# NinjaPool-171016.net
KiCad netlist of a schematic drawn in EAGLE
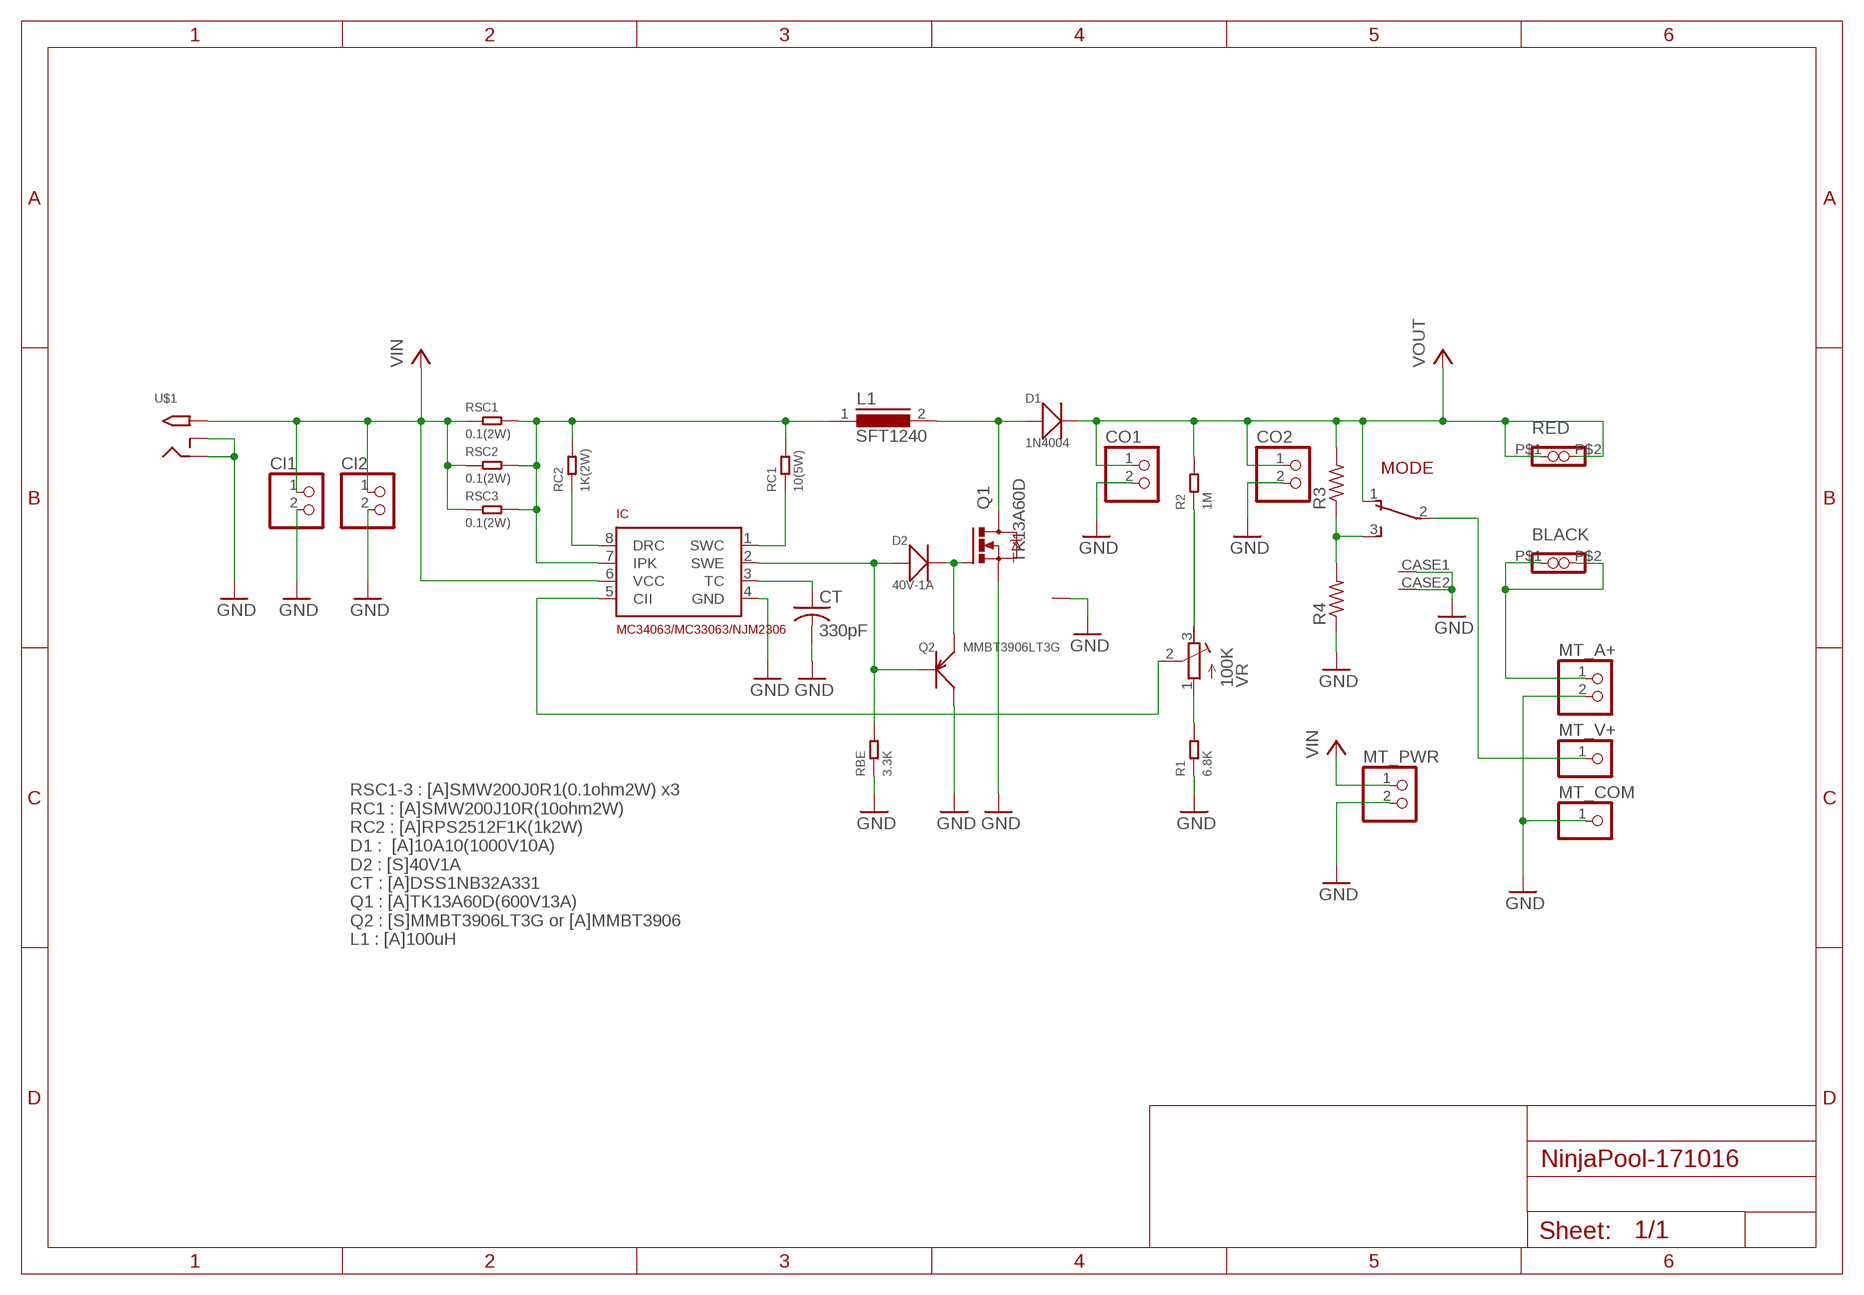
[diagram p0: schematic, sheet 1]

(export (version "E")
  (design (tool "Eeschema 10.0.6"))
  (components
    (comp (ref "BLACK")
      (value "BANANA1")
      (footprint "eagle-import:BANANA")
      (libsource (lib "eagle-import") (part "BANANA1"))
    )
    (comp (ref "CI1")
      (value "PINHD-1X2")
      (footprint "eagle-import:1X02")
      (libsource (lib "eagle-import") (part "PINHD-1X2"))
    )
    (comp (ref "CI2")
      (value "PINHD-1X2")
      (footprint "eagle-import:1X02")
      (libsource (lib "eagle-import") (part "PINHD-1X2"))
    )
    (comp (ref "CO1")
      (value "PINHD-1X2")
      (footprint "eagle-import:1X02")
      (libsource (lib "eagle-import") (part "PINHD-1X2"))
    )
    (comp (ref "CO2")
      (value "PINHD-1X2")
      (footprint "eagle-import:1X02")
      (libsource (lib "eagle-import") (part "PINHD-1X2"))
    )
    (comp (ref "CT")
      (value "330pF")
      (footprint "eagle-import:C050-024X044")
      (libsource (lib "eagle-import") (part "C-US050-024X044"))
    )
    (comp (ref "D1")
      (value "1N4004")
      (footprint "eagle-import:DO-41")
      (libsource (lib "eagle-import") (part "DIP-DIODE-400V-1A(DO-41)"))
    )
    (comp (ref "D2")
      (value "40V-1A")
      (footprint "eagle-import:DO-214AC")
      (fields (field (name "MPN") "1N5819"))
      (libsource (lib "eagle-import") (part "SMD-DIODE-SCHOTTKY-40V-1A(DO-214AC)"))
    )
    (comp (ref "HEAT")
      (value "HEAT111PB015")
      (footprint "eagle-import:HEAT11PB015")
      (libsource (lib "eagle-import") (part "HEAT111PB015"))
    )
    (comp (ref "IC")
      (value "MC34063/MC33063/NJM2306")
      (footprint "eagle-import:DIL8")
      (libsource (lib "eagle-import") (part "MC34063/MC33063/NJM2306"))
    )
    (comp (ref "L1")
      (value "SFT1240")
      (footprint "eagle-import:SFT1240")
      (libsource (lib "eagle-import") (part "SFT1240"))
    )
    (comp (ref "MODE")
      (value "4MS1R202M6QES")
      (footprint "eagle-import:4MS1R202M6QES")
      (libsource (lib "eagle-import") (part "4MS1R202M6QES"))
    )
    (comp (ref "MT_A+")
      (value "PINHD-1X2")
      (footprint "eagle-import:1X02")
      (libsource (lib "eagle-import") (part "PINHD-1X2"))
    )
    (comp (ref "MT_COM")
      (value "PINHD-1X1")
      (footprint "eagle-import:1X01")
      (libsource (lib "eagle-import") (part "PINHD-1X1"))
    )
    (comp (ref "MT_PWR")
      (value "PINHD-1X2")
      (footprint "eagle-import:1X02")
      (libsource (lib "eagle-import") (part "PINHD-1X2"))
    )
    (comp (ref "MT_V+")
      (value "PINHD-1X1")
      (footprint "eagle-import:1X01")
      (libsource (lib "eagle-import") (part "PINHD-1X1"))
    )
    (comp (ref "Q1")
      (value "TK13A60D")
      (footprint "eagle-import:TO220BV")
      (libsource (lib "eagle-import") (part "IRF520"))
    )
    (comp (ref "Q2")
      (value "MMBT3906LT3G")
      (footprint "eagle-import:SOT-23")
      (libsource (lib "eagle-import") (part "SMD-TRANSISTORS-PNP-40V-200MA-MMBT3906LT3G(SOT-23)"))
    )
    (comp (ref "R1")
      (value "6.8K")
      (footprint "eagle-import:R0603")
      (fields (field (name "MPN") "RC0805JR-07220KL"))
      (libsource (lib "eagle-import") (part "SMD-RES-6.8K-1%-1/10W(0603)"))
    )
    (comp (ref "R2")
      (value "1M")
      (footprint "eagle-import:R0603")
      (fields (field (name "MPN") "RC0603FR-071ML"))
      (libsource (lib "eagle-import") (part "SMD-RES-1M-1%-1/10W(0603)"))
    )
    (comp (ref "R3")
      (value "R-US_R0603")
      (footprint "eagle-import:R0603")
      (libsource (lib "eagle-import") (part "R-US_R0603"))
    )
    (comp (ref "R4")
      (value "R-US_R0603")
      (footprint "eagle-import:R0603")
      (libsource (lib "eagle-import") (part "R-US_R0603"))
    )
    (comp (ref "RBE")
      (value "3.3K")
      (footprint "eagle-import:R0603")
      (libsource (lib "eagle-import") (part "SMD-RES-3.3K-5%-1/10W(0603)"))
    )
    (comp (ref "RC1")
      (value "10(5W)")
      (footprint "eagle-import:SWE500")
      (libsource (lib "eagle-import") (part "SWE500"))
    )
    (comp (ref "RC2")
      (value "1K(2W)")
      (footprint "eagle-import:R2512")
      (libsource (lib "eagle-import") (part "R2512"))
    )
    (comp (ref "RED")
      (value "BANANA1")
      (footprint "eagle-import:BANANA")
      (libsource (lib "eagle-import") (part "BANANA1"))
    )
    (comp (ref "RSC1")
      (value "0.1(2W)")
      (footprint "eagle-import:SMW200")
      (libsource (lib "eagle-import") (part "SWE200"))
    )
    (comp (ref "RSC2")
      (value "0.1(2W)")
      (footprint "eagle-import:SMW200")
      (libsource (lib "eagle-import") (part "SWE200"))
    )
    (comp (ref "RSC3")
      (value "0.1(2W)")
      (footprint "eagle-import:SMW200")
      (libsource (lib "eagle-import") (part "SWE200"))
    )
    (comp (ref "U$1")
      (value "2.1MMJACKTHM")
      (footprint "eagle-import:PJ-102A")
      (libsource (lib "eagle-import") (part "2.1MMJACKTHM"))
    )
    (comp (ref "VR")
      (value "100K")
      (footprint "eagle-import:AITENDO_R16K1")
      (libsource (lib "eagle-import") (part "R-TRIMMAITENDO_R16K1"))
    )
  )
  (nets
    (net (code "1") (name "GND") (class "Default")
      (node (ref "CI1") (pin "2") (pinfunction "2_2") (pintype "passive"))
      (node (ref "CI2") (pin "2") (pinfunction "2_2") (pintype "passive"))
      (node (ref "CO1") (pin "2") (pinfunction "2_2") (pintype "passive"))
      (node (ref "CO2") (pin "2") (pinfunction "2_2") (pintype "passive"))
      (node (ref "CT") (pin "2") (pinfunction "2_2") (pintype "passive"))
      (node (ref "HEAT") (pin "P$1") (pinfunction "P$1_P$1") (pintype "bidirectional"))
      (node (ref "IC") (pin "4") (pinfunction "GND_4") (pintype "bidirectional"))
      (node (ref "MODE") (pin "CASE1") (pinfunction "CASE1_CASE1") (pintype "passive"))
      (node (ref "MODE") (pin "CASE2") (pinfunction "CASE2_CASE2") (pintype "passive"))
      (node (ref "MT_A+") (pin "2") (pinfunction "2_2") (pintype "passive"))
      (node (ref "MT_COM") (pin "1") (pinfunction "1_1") (pintype "passive"))
      (node (ref "MT_PWR") (pin "2") (pinfunction "2_2") (pintype "passive"))
      (node (ref "Q1") (pin "S") (pinfunction "S_S") (pintype "passive"))
      (node (ref "Q2") (pin "3") (pinfunction "C_3") (pintype "passive"))
      (node (ref "R1") (pin "1") (pinfunction "1_1") (pintype "passive"))
      (node (ref "R4") (pin "1") (pinfunction "1_1") (pintype "passive"))
      (node (ref "RBE") (pin "1") (pinfunction "1_1") (pintype "passive"))
      (node (ref "U$1") (pin "RING") (pinfunction "RING_RING") (pintype "bidirectional"))
      (node (ref "U$1") (pin "RING_SW") (pinfunction "RING_SW_RING_SW") (pintype "bidirectional"))
    )
    (net (code "2") (name "Net-(BLACK-1)") (class "Default")
      (node (ref "BLACK") (pin "P$1") (pinfunction "1_P$1") (pintype "passive"))
      (node (ref "BLACK") (pin "P$2") (pinfunction "2_P$2") (pintype "passive"))
      (node (ref "MT_A+") (pin "1") (pinfunction "1_1") (pintype "passive"))
    )
    (net (code "3") (name "Net-(D1-+)") (class "Default")
      (node (ref "D1") (pin "1") (pinfunction "+_1") (pintype "passive"))
      (node (ref "L1") (pin "2") (pinfunction "2_2") (pintype "passive"))
      (node (ref "Q1") (pin "D") (pinfunction "D_D") (pintype "passive"))
    )
    (net (code "4") (name "Net-(D2-+)") (class "Default")
      (node (ref "D2") (pin "1") (pinfunction "+_1") (pintype "passive"))
      (node (ref "IC") (pin "2") (pinfunction "SWE_2") (pintype "bidirectional"))
      (node (ref "Q2") (pin "1") (pinfunction "B_1") (pintype "passive"))
      (node (ref "RBE") (pin "2") (pinfunction "2_2") (pintype "passive"))
    )
    (net (code "5") (name "Net-(D2--)") (class "Default")
      (node (ref "D2") (pin "2") (pinfunction "-_2") (pintype "passive"))
      (node (ref "Q1") (pin "G") (pinfunction "G_G") (pintype "passive"))
      (node (ref "Q2") (pin "2") (pinfunction "E_2") (pintype "passive"))
    )
    (net (code "6") (name "Net-(IC-CII)") (class "Default")
      (node (ref "IC") (pin "5") (pinfunction "CII_5") (pintype "bidirectional"))
      (node (ref "VR") (pin "2") (pinfunction "S_2") (pintype "passive"))
    )
    (net (code "7") (name "Net-(IC-DRC)") (class "Default")
      (node (ref "IC") (pin "8") (pinfunction "DRC_8") (pintype "bidirectional"))
      (node (ref "RC2") (pin "1") (pinfunction "1_1") (pintype "passive"))
    )
    (net (code "8") (name "Net-(IC-IPK)") (class "Default")
      (node (ref "IC") (pin "7") (pinfunction "IPK_7") (pintype "bidirectional"))
      (node (ref "L1") (pin "1") (pinfunction "1_1") (pintype "passive"))
      (node (ref "RC1") (pin "2") (pinfunction "2_2") (pintype "passive"))
      (node (ref "RC2") (pin "2") (pinfunction "2_2") (pintype "passive"))
      (node (ref "RSC1") (pin "2") (pinfunction "2_2") (pintype "passive"))
      (node (ref "RSC2") (pin "2") (pinfunction "2_2") (pintype "passive"))
      (node (ref "RSC3") (pin "2") (pinfunction "2_2") (pintype "passive"))
    )
    (net (code "9") (name "Net-(IC-SWC)") (class "Default")
      (node (ref "IC") (pin "1") (pinfunction "SWC_1") (pintype "bidirectional"))
      (node (ref "RC1") (pin "1") (pinfunction "1_1") (pintype "passive"))
    )
    (net (code "10") (name "Net-(IC-TC)") (class "Default")
      (node (ref "CT") (pin "1") (pinfunction "1_1") (pintype "passive"))
      (node (ref "IC") (pin "3") (pinfunction "TC_3") (pintype "bidirectional"))
    )
    (net (code "11") (name "Net-(MODE-Pad2)") (class "Default")
      (node (ref "MODE") (pin "2") (pinfunction "2_2") (pintype "passive"))
      (node (ref "MT_V+") (pin "1") (pinfunction "1_1") (pintype "passive"))
    )
    (net (code "12") (name "Net-(MODE-Pad3)") (class "Default")
      (node (ref "MODE") (pin "3") (pinfunction "3_3") (pintype "passive"))
      (node (ref "R3") (pin "1") (pinfunction "1_1") (pintype "passive"))
      (node (ref "R4") (pin "2") (pinfunction "2_2") (pintype "passive"))
    )
    (net (code "13") (name "Net-(VR-A)") (class "Default")
      (node (ref "R1") (pin "2") (pinfunction "2_2") (pintype "passive"))
      (node (ref "VR") (pin "1") (pinfunction "A_1") (pintype "passive"))
    )
    (net (code "14") (name "Net-(VR-E)") (class "Default")
      (node (ref "R2") (pin "1") (pinfunction "1_1") (pintype "passive"))
      (node (ref "VR") (pin "3") (pinfunction "E_3") (pintype "passive"))
    )
    (net (code "15") (name "VIN") (class "Default")
      (node (ref "CI1") (pin "1") (pinfunction "1_1") (pintype "passive"))
      (node (ref "CI2") (pin "1") (pinfunction "1_1") (pintype "passive"))
      (node (ref "IC") (pin "6") (pinfunction "VCC_6") (pintype "bidirectional"))
      (node (ref "MT_PWR") (pin "1") (pinfunction "1_1") (pintype "passive"))
      (node (ref "RSC1") (pin "1") (pinfunction "1_1") (pintype "passive"))
      (node (ref "RSC2") (pin "1") (pinfunction "1_1") (pintype "passive"))
      (node (ref "RSC3") (pin "1") (pinfunction "1_1") (pintype "passive"))
      (node (ref "U$1") (pin "TIP") (pinfunction "TIP_TIP") (pintype "bidirectional"))
    )
    (net (code "16") (name "VOUT") (class "Default")
      (node (ref "CO1") (pin "1") (pinfunction "1_1") (pintype "passive"))
      (node (ref "CO2") (pin "1") (pinfunction "1_1") (pintype "passive"))
      (node (ref "D1") (pin "2") (pinfunction "-_2") (pintype "passive"))
      (node (ref "MODE") (pin "1") (pinfunction "1_1") (pintype "passive"))
      (node (ref "R2") (pin "2") (pinfunction "2_2") (pintype "passive"))
      (node (ref "R3") (pin "2") (pinfunction "2_2") (pintype "passive"))
      (node (ref "RED") (pin "P$1") (pinfunction "1_P$1") (pintype "passive"))
      (node (ref "RED") (pin "P$2") (pinfunction "2_P$2") (pintype "passive"))
    )
  )
)
